# status_led_base.net
KiCad netlist of a schematic drawn in EAGLE
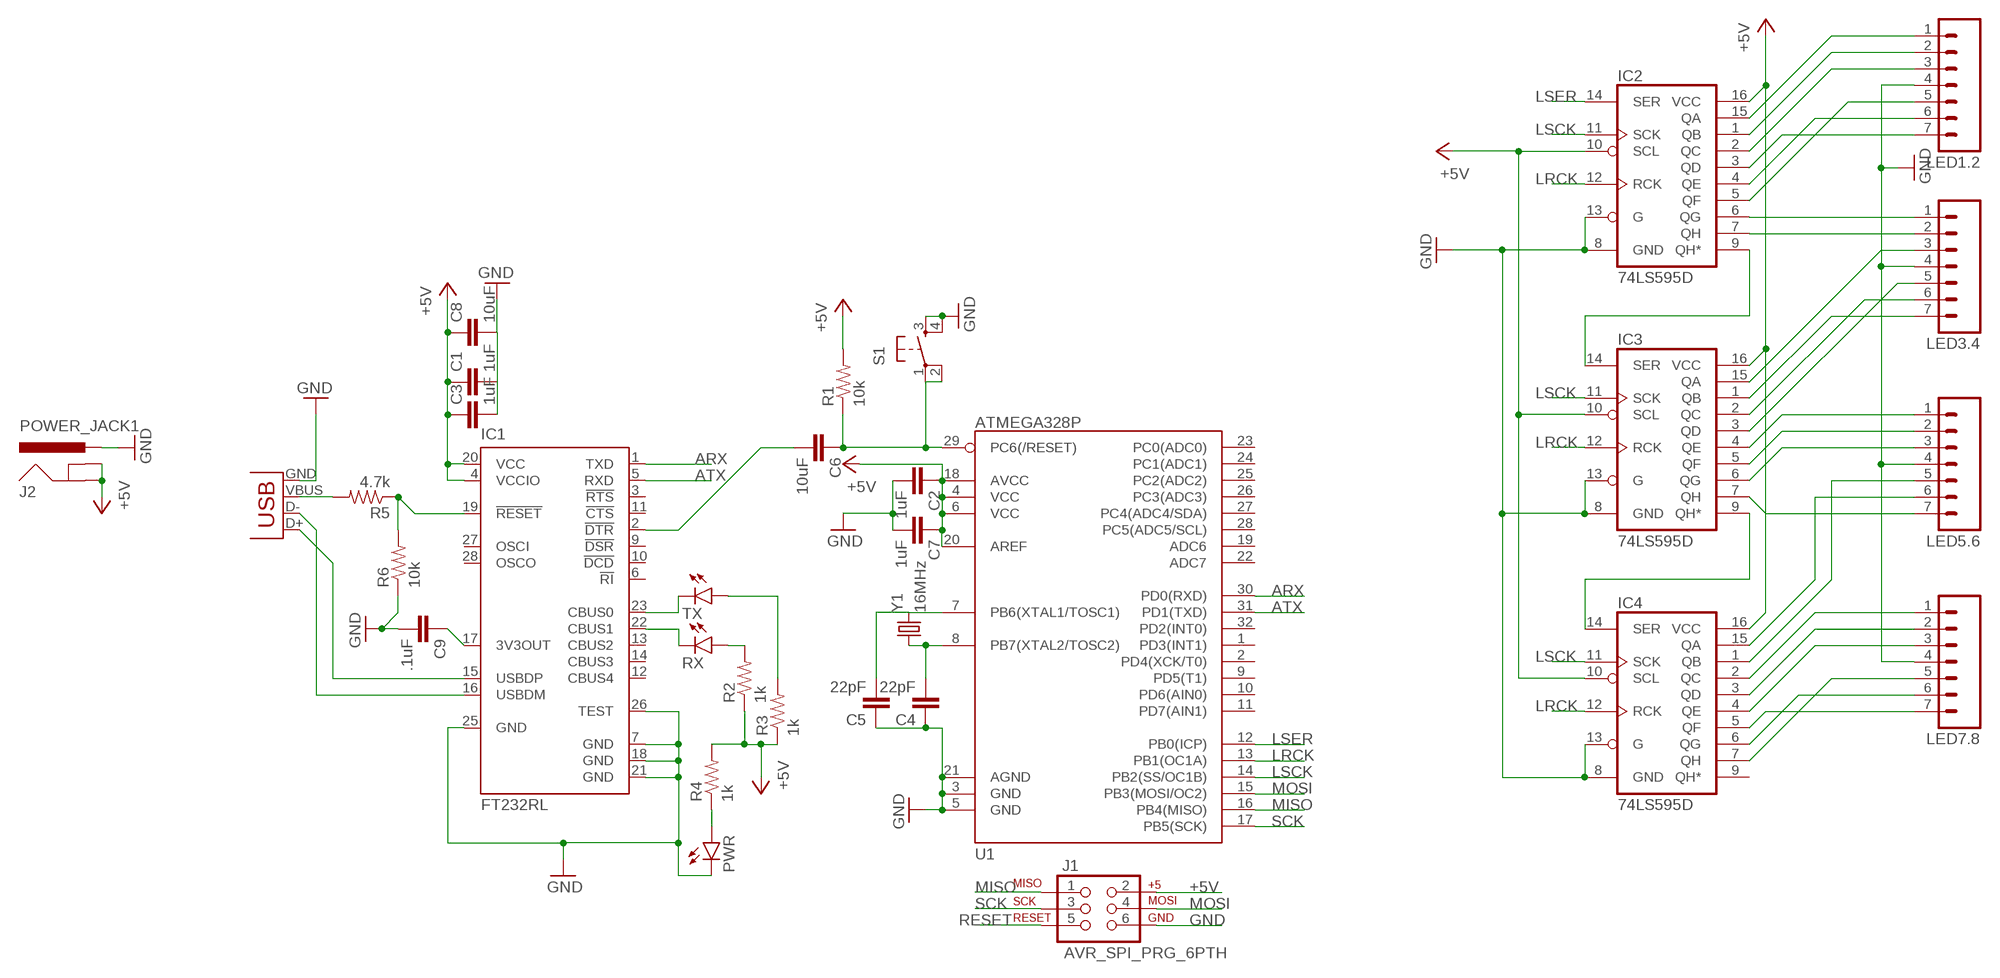
[diagram p0: schematic, sheet 1]

(export (version "E")
  (design (tool "Eeschema 10.0.6"))
  (components
    (comp (ref "C1")
      (value "1uF")
      (footprint "eagle-import:0603-CAP")
      (libsource (lib "eagle-import") (part "CAP0603-CAP"))
    )
    (comp (ref "C2")
      (value "1uF")
      (footprint "eagle-import:0603-CAP")
      (libsource (lib "eagle-import") (part "CAP0603-CAP"))
    )
    (comp (ref "C3")
      (value "1uF")
      (footprint "eagle-import:0603-CAP")
      (libsource (lib "eagle-import") (part "CAP0603-CAP"))
    )
    (comp (ref "C4")
      (value "22pF")
      (footprint "eagle-import:0603-CAP")
      (libsource (lib "eagle-import") (part "CAP0603-CAP"))
    )
    (comp (ref "C5")
      (value "22pF")
      (footprint "eagle-import:0603-CAP")
      (libsource (lib "eagle-import") (part "CAP0603-CAP"))
    )
    (comp (ref "C6")
      (value "10uF")
      (footprint "eagle-import:0603-CAP")
      (libsource (lib "eagle-import") (part "CAP0603-CAP"))
    )
    (comp (ref "C7")
      (value "1uF")
      (footprint "eagle-import:0603-CAP")
      (libsource (lib "eagle-import") (part "CAP0603-CAP"))
    )
    (comp (ref "C8")
      (value "10uF")
      (footprint "eagle-import:0603-CAP")
      (libsource (lib "eagle-import") (part "CAP0603-CAP"))
    )
    (comp (ref "C9")
      (value ".1uF")
      (footprint "eagle-import:0603-CAP")
      (libsource (lib "eagle-import") (part "CAP0603-CAP"))
    )
    (comp (ref "IC1")
      (value "FT232RL")
      (footprint "eagle-import:SSOP28")
      (libsource (lib "eagle-import") (part "FT232RL"))
    )
    (comp (ref "IC2")
      (value "74LS595D")
      (footprint "eagle-import:SO16")
      (libsource (lib "eagle-import") (part "74595DLS"))
    )
    (comp (ref "IC3")
      (value "74LS595D")
      (footprint "eagle-import:SO16")
      (libsource (lib "eagle-import") (part "74595DLS"))
    )
    (comp (ref "IC4")
      (value "74LS595D")
      (footprint "eagle-import:SO16")
      (libsource (lib "eagle-import") (part "74595DLS"))
    )
    (comp (ref "J1")
      (value "AVR_SPI_PRG_6PTH")
      (footprint "eagle-import:2X3")
      (libsource (lib "eagle-import") (part "AVR_SPI_PRG_6PTH"))
    )
    (comp (ref "J2")
      (value "POWER_JACK1")
      (footprint "eagle-import:POWER_JACK_SMD_OVERPASTE_REDBOARD_0603")
      (libsource (lib "eagle-import") (part "POWER_JACK1"))
    )
    (comp (ref "JP1")
      (value "USBSMD")
      (footprint "eagle-import:USB-MINIB")
      (libsource (lib "eagle-import") (part "USBSMD"))
    )
    (comp (ref "LED1.2")
      (value "M07")
      (footprint "eagle-import:1X07")
      (libsource (lib "eagle-import") (part "M07"))
    )
    (comp (ref "LED3.4")
      (value "M07")
      (footprint "eagle-import:1X07")
      (libsource (lib "eagle-import") (part "M07"))
    )
    (comp (ref "LED5.6")
      (value "M07")
      (footprint "eagle-import:1X07")
      (libsource (lib "eagle-import") (part "M07"))
    )
    (comp (ref "LED7.8")
      (value "M07")
      (footprint "eagle-import:1X07")
      (libsource (lib "eagle-import") (part "M07"))
    )
    (comp (ref "PWR")
      (value "LED0603")
      (footprint "eagle-import:LED-0603")
      (libsource (lib "eagle-import") (part "LED0603"))
    )
    (comp (ref "R1")
      (value "10k")
      (footprint "eagle-import:0603-RES")
      (libsource (lib "eagle-import") (part "RESISTOR0603-RES"))
    )
    (comp (ref "R2")
      (value "1k")
      (footprint "eagle-import:0603-RES")
      (libsource (lib "eagle-import") (part "RESISTOR0603-RES"))
    )
    (comp (ref "R3")
      (value "1k")
      (footprint "eagle-import:0603-RES")
      (libsource (lib "eagle-import") (part "RESISTOR0603-RES"))
    )
    (comp (ref "R4")
      (value "1k")
      (footprint "eagle-import:0603-RES")
      (libsource (lib "eagle-import") (part "RESISTOR0603-RES"))
    )
    (comp (ref "R5")
      (value "4.7k")
      (footprint "eagle-import:0603-RES")
      (libsource (lib "eagle-import") (part "RESISTOR0603-RES"))
    )
    (comp (ref "R6")
      (value "10k")
      (footprint "eagle-import:0603-RES")
      (libsource (lib "eagle-import") (part "RESISTOR0603-RES"))
    )
    (comp (ref "RX")
      (value "LED0603")
      (footprint "eagle-import:LED-0603")
      (libsource (lib "eagle-import") (part "LED0603"))
    )
    (comp (ref "S1")
      (value "TAC_SWITCHSMD")
      (footprint "eagle-import:TACTILE-SWITCH-SMD")
      (libsource (lib "eagle-import") (part "TAC_SWITCHSMD"))
    )
    (comp (ref "TX")
      (value "LED0603")
      (footprint "eagle-import:LED-0603")
      (libsource (lib "eagle-import") (part "LED0603"))
    )
    (comp (ref "U1")
      (value "ATMEGA328P")
      (footprint "eagle-import:TQFP32-08")
      (libsource (lib "eagle-import") (part "ATMEGA328_SMT"))
    )
    (comp (ref "Y1")
      (value "16MHz")
      (footprint "eagle-import:HC49UP")
      (libsource (lib "eagle-import") (part "CRYSTALSMD"))
    )
  )
  (nets
    (net (code "1") (name "+5V") (class "Default")
      (node (ref "C1") (pin "1") (pinfunction "1_1") (pintype "passive"))
      (node (ref "C2") (pin "1") (pinfunction "1_1") (pintype "passive"))
      (node (ref "C3") (pin "1") (pinfunction "1_1") (pintype "passive"))
      (node (ref "C7") (pin "1") (pinfunction "1_1") (pintype "passive"))
      (node (ref "C8") (pin "1") (pinfunction "1_1") (pintype "passive"))
      (node (ref "IC1") (pin "20") (pinfunction "VCC_20") (pintype "power_in"))
      (node (ref "IC1") (pin "4") (pinfunction "VCCIO_4") (pintype "power_in"))
      (node (ref "IC2") (pin "10") (pinfunction "SCL_10") (pintype "input"))
      (node (ref "IC2") (pin "16") (pinfunction "VCC_16") (pintype "power_in"))
      (node (ref "IC3") (pin "10") (pinfunction "SCL_10") (pintype "input"))
      (node (ref "IC3") (pin "16") (pinfunction "VCC_16") (pintype "power_in"))
      (node (ref "IC4") (pin "10") (pinfunction "SCL_10") (pintype "input"))
      (node (ref "IC4") (pin "16") (pinfunction "VCC_16") (pintype "power_in"))
      (node (ref "J1") (pin "2") (pinfunction "2_2") (pintype "passive"))
      (node (ref "J2") (pin "GND") (pinfunction "GNDBREAK_GND") (pintype "bidirectional"))
      (node (ref "J2") (pin "P$4") (pinfunction "GND_P$4") (pintype "bidirectional"))
      (node (ref "R1") (pin "2") (pinfunction "2_2") (pintype "passive"))
      (node (ref "R2") (pin "1") (pinfunction "1_1") (pintype "passive"))
      (node (ref "R3") (pin "1") (pinfunction "1_1") (pintype "passive"))
      (node (ref "R4") (pin "2") (pinfunction "2_2") (pintype "passive"))
      (node (ref "U1") (pin "18") (pinfunction "AVCC_18") (pintype "bidirectional"))
      (node (ref "U1") (pin "20") (pinfunction "AREF_20") (pintype "bidirectional"))
      (node (ref "U1") (pin "4") (pinfunction "VCC_4") (pintype "bidirectional"))
      (node (ref "U1") (pin "6") (pinfunction "VCC_6") (pintype "bidirectional"))
    )
    (net (code "2") (name "/ARX") (class "Default")
      (node (ref "IC1") (pin "1") (pinfunction "TXD_1") (pintype "output"))
      (node (ref "U1") (pin "30") (pinfunction "PD0(RXD)_30") (pintype "bidirectional"))
    )
    (net (code "3") (name "/ATX") (class "Default")
      (node (ref "IC1") (pin "5") (pinfunction "RXD_5") (pintype "input"))
      (node (ref "U1") (pin "31") (pinfunction "PD1(TXD)_31") (pintype "bidirectional"))
    )
    (net (code "4") (name "/LRCK") (class "Default")
      (node (ref "IC2") (pin "12") (pinfunction "RCK_12") (pintype "input"))
      (node (ref "IC3") (pin "12") (pinfunction "RCK_12") (pintype "input"))
      (node (ref "IC4") (pin "12") (pinfunction "RCK_12") (pintype "input"))
      (node (ref "U1") (pin "13") (pinfunction "PB1(OC1A)_13") (pintype "bidirectional"))
    )
    (net (code "5") (name "/LSCK") (class "Default")
      (node (ref "IC2") (pin "11") (pinfunction "SCK_11") (pintype "input"))
      (node (ref "IC3") (pin "11") (pinfunction "SCK_11") (pintype "input"))
      (node (ref "IC4") (pin "11") (pinfunction "SCK_11") (pintype "input"))
      (node (ref "U1") (pin "14") (pinfunction "PB2(SS/OC1B)_14") (pintype "bidirectional"))
    )
    (net (code "6") (name "/LSER") (class "Default")
      (node (ref "IC2") (pin "14") (pinfunction "SER_14") (pintype "input"))
      (node (ref "U1") (pin "12") (pinfunction "PB0(ICP)_12") (pintype "bidirectional"))
    )
    (net (code "7") (name "/MISO") (class "Default")
      (node (ref "J1") (pin "1") (pinfunction "1_1") (pintype "passive"))
      (node (ref "U1") (pin "16") (pinfunction "PB4(MISO)_16") (pintype "bidirectional"))
    )
    (net (code "8") (name "/MOSI") (class "Default")
      (node (ref "J1") (pin "4") (pinfunction "4_4") (pintype "passive"))
      (node (ref "U1") (pin "15") (pinfunction "PB3(MOSI/OC2)_15") (pintype "bidirectional"))
    )
    (net (code "9") (name "/RESET") (class "Default")
      (node (ref "C6") (pin "1") (pinfunction "1_1") (pintype "passive"))
      (node (ref "J1") (pin "5") (pinfunction "5_5") (pintype "passive"))
      (node (ref "R1") (pin "1") (pinfunction "1_1") (pintype "passive"))
      (node (ref "S1") (pin "1") (pinfunction "1_1") (pintype "passive"))
      (node (ref "S1") (pin "2") (pinfunction "2_2") (pintype "passive"))
      (node (ref "U1") (pin "29") (pinfunction "PC6(/RESET)_29") (pintype "bidirectional"))
    )
    (net (code "10") (name "/SCK") (class "Default")
      (node (ref "J1") (pin "3") (pinfunction "3_3") (pintype "passive"))
      (node (ref "U1") (pin "17") (pinfunction "PB5(SCK)_17") (pintype "bidirectional"))
    )
    (net (code "11") (name "GND") (class "Default")
      (node (ref "C1") (pin "2") (pinfunction "2_2") (pintype "passive"))
      (node (ref "C2") (pin "2") (pinfunction "2_2") (pintype "passive"))
      (node (ref "C3") (pin "2") (pinfunction "2_2") (pintype "passive"))
      (node (ref "C4") (pin "1") (pinfunction "1_1") (pintype "passive"))
      (node (ref "C5") (pin "1") (pinfunction "1_1") (pintype "passive"))
      (node (ref "C7") (pin "2") (pinfunction "2_2") (pintype "passive"))
      (node (ref "C8") (pin "2") (pinfunction "2_2") (pintype "passive"))
      (node (ref "C9") (pin "2") (pinfunction "2_2") (pintype "passive"))
      (node (ref "IC1") (pin "18") (pinfunction "GND_18") (pintype "power_in"))
      (node (ref "IC1") (pin "21") (pinfunction "GND_21") (pintype "power_in"))
      (node (ref "IC1") (pin "25") (pinfunction "GND_25") (pintype "power_in"))
      (node (ref "IC1") (pin "26") (pinfunction "TEST_26") (pintype "input"))
      (node (ref "IC1") (pin "7") (pinfunction "GND_7") (pintype "power_in"))
      (node (ref "IC2") (pin "13") (pinfunction "G_13") (pintype "input"))
      (node (ref "IC2") (pin "8") (pinfunction "GND_8") (pintype "power_in"))
      (node (ref "IC3") (pin "13") (pinfunction "G_13") (pintype "input"))
      (node (ref "IC3") (pin "8") (pinfunction "GND_8") (pintype "power_in"))
      (node (ref "IC4") (pin "13") (pinfunction "G_13") (pintype "input"))
      (node (ref "IC4") (pin "8") (pinfunction "GND_8") (pintype "power_in"))
      (node (ref "J1") (pin "6") (pinfunction "6_6") (pintype "passive"))
      (node (ref "J2") (pin "VIN0") (pinfunction "PWR_VIN0") (pintype "bidirectional"))
      (node (ref "JP1") (pin "GND") (pinfunction "GND_GND") (pintype "bidirectional"))
      (node (ref "LED1.2") (pin "4") (pinfunction "4_4") (pintype "passive"))
      (node (ref "LED3.4") (pin "4") (pinfunction "4_4") (pintype "passive"))
      (node (ref "LED5.6") (pin "4") (pinfunction "4_4") (pintype "passive"))
      (node (ref "LED7.8") (pin "4") (pinfunction "4_4") (pintype "passive"))
      (node (ref "PWR") (pin "C") (pinfunction "C_C") (pintype "passive"))
      (node (ref "R6") (pin "1") (pinfunction "1_1") (pintype "passive"))
      (node (ref "S1") (pin "3") (pinfunction "3_3") (pintype "passive"))
      (node (ref "S1") (pin "4") (pinfunction "4_4") (pintype "passive"))
      (node (ref "U1") (pin "21") (pinfunction "AGND_21") (pintype "bidirectional"))
      (node (ref "U1") (pin "3") (pinfunction "GND_3") (pintype "bidirectional"))
      (node (ref "U1") (pin "5") (pinfunction "GND_5") (pintype "bidirectional"))
    )
    (net (code "12") (name "Net-(IC1-3V3OUT)") (class "Default")
      (node (ref "C9") (pin "1") (pinfunction "1_1") (pintype "passive"))
      (node (ref "IC1") (pin "17") (pinfunction "3V3OUT_17") (pintype "output"))
    )
    (net (code "13") (name "Net-(IC1-CBUS0)") (class "Default")
      (node (ref "IC1") (pin "23") (pinfunction "CBUS0_23") (pintype "bidirectional"))
      (node (ref "TX") (pin "C") (pinfunction "C_C") (pintype "passive"))
    )
    (net (code "14") (name "Net-(IC1-CBUS1)") (class "Default")
      (node (ref "IC1") (pin "22") (pinfunction "CBUS1_22") (pintype "bidirectional"))
      (node (ref "RX") (pin "C") (pinfunction "C_C") (pintype "passive"))
    )
    (net (code "15") (name "Net-(IC1-USBDM)") (class "Default")
      (node (ref "IC1") (pin "16") (pinfunction "USBDM_16") (pintype "bidirectional"))
      (node (ref "JP1") (pin "D-") (pinfunction "D-_D-") (pintype "bidirectional"))
    )
    (net (code "16") (name "Net-(IC1-USBDP)") (class "Default")
      (node (ref "IC1") (pin "15") (pinfunction "USBDP_15") (pintype "bidirectional"))
      (node (ref "JP1") (pin "D+") (pinfunction "D+_D+") (pintype "bidirectional"))
    )
    (net (code "17") (name "Net-(IC1-~{DTR})") (class "Default")
      (node (ref "C6") (pin "2") (pinfunction "2_2") (pintype "passive"))
      (node (ref "IC1") (pin "2") (pinfunction "~{DTR}_2") (pintype "output"))
    )
    (net (code "18") (name "Net-(IC1-~{RESET})") (class "Default")
      (node (ref "IC1") (pin "19") (pinfunction "~{RESET}_19") (pintype "input"))
      (node (ref "R5") (pin "1") (pinfunction "1_1") (pintype "passive"))
      (node (ref "R6") (pin "2") (pinfunction "2_2") (pintype "passive"))
    )
    (net (code "19") (name "Net-(IC2-QA)") (class "Default")
      (node (ref "IC2") (pin "15") (pinfunction "QA_15") (pintype "tri_state"))
      (node (ref "LED1.2") (pin "1") (pinfunction "1_1") (pintype "passive"))
    )
    (net (code "20") (name "Net-(IC2-QB)") (class "Default")
      (node (ref "IC2") (pin "1") (pinfunction "QB_1") (pintype "tri_state"))
      (node (ref "LED1.2") (pin "2") (pinfunction "2_2") (pintype "passive"))
    )
    (net (code "21") (name "Net-(IC2-QC)") (class "Default")
      (node (ref "IC2") (pin "2") (pinfunction "QC_2") (pintype "tri_state"))
      (node (ref "LED1.2") (pin "3") (pinfunction "3_3") (pintype "passive"))
    )
    (net (code "22") (name "Net-(IC2-QD)") (class "Default")
      (node (ref "IC2") (pin "3") (pinfunction "QD_3") (pintype "tri_state"))
      (node (ref "LED1.2") (pin "7") (pinfunction "7_7") (pintype "passive"))
    )
    (net (code "23") (name "Net-(IC2-QE)") (class "Default")
      (node (ref "IC2") (pin "4") (pinfunction "QE_4") (pintype "tri_state"))
      (node (ref "LED1.2") (pin "6") (pinfunction "6_6") (pintype "passive"))
    )
    (net (code "24") (name "Net-(IC2-QF)") (class "Default")
      (node (ref "IC2") (pin "5") (pinfunction "QF_5") (pintype "tri_state"))
      (node (ref "LED1.2") (pin "5") (pinfunction "5_5") (pintype "passive"))
    )
    (net (code "25") (name "Net-(IC2-QG)") (class "Default")
      (node (ref "IC2") (pin "6") (pinfunction "QG_6") (pintype "tri_state"))
      (node (ref "LED3.4") (pin "1") (pinfunction "1_1") (pintype "passive"))
    )
    (net (code "26") (name "Net-(IC2-QH)") (class "Default")
      (node (ref "IC2") (pin "7") (pinfunction "QH_7") (pintype "tri_state"))
      (node (ref "LED3.4") (pin "2") (pinfunction "2_2") (pintype "passive"))
    )
    (net (code "27") (name "Net-(IC2-QH*)") (class "Default")
      (node (ref "IC2") (pin "9") (pinfunction "QH*_9") (pintype "tri_state"))
      (node (ref "IC3") (pin "14") (pinfunction "SER_14") (pintype "input"))
    )
    (net (code "28") (name "Net-(IC3-QA)") (class "Default")
      (node (ref "IC3") (pin "15") (pinfunction "QA_15") (pintype "tri_state"))
      (node (ref "LED3.4") (pin "3") (pinfunction "3_3") (pintype "passive"))
    )
    (net (code "29") (name "Net-(IC3-QB)") (class "Default")
      (node (ref "IC3") (pin "1") (pinfunction "QB_1") (pintype "tri_state"))
      (node (ref "LED3.4") (pin "7") (pinfunction "7_7") (pintype "passive"))
    )
    (net (code "30") (name "Net-(IC3-QC)") (class "Default")
      (node (ref "IC3") (pin "2") (pinfunction "QC_2") (pintype "tri_state"))
      (node (ref "LED3.4") (pin "6") (pinfunction "6_6") (pintype "passive"))
    )
    (net (code "31") (name "Net-(IC3-QD)") (class "Default")
      (node (ref "IC3") (pin "3") (pinfunction "QD_3") (pintype "tri_state"))
      (node (ref "LED3.4") (pin "5") (pinfunction "5_5") (pintype "passive"))
    )
    (net (code "32") (name "Net-(IC3-QE)") (class "Default")
      (node (ref "IC3") (pin "4") (pinfunction "QE_4") (pintype "tri_state"))
      (node (ref "LED5.6") (pin "1") (pinfunction "1_1") (pintype "passive"))
    )
    (net (code "33") (name "Net-(IC3-QF)") (class "Default")
      (node (ref "IC3") (pin "5") (pinfunction "QF_5") (pintype "tri_state"))
      (node (ref "LED5.6") (pin "2") (pinfunction "2_2") (pintype "passive"))
    )
    (net (code "34") (name "Net-(IC3-QG)") (class "Default")
      (node (ref "IC3") (pin "6") (pinfunction "QG_6") (pintype "tri_state"))
      (node (ref "LED5.6") (pin "3") (pinfunction "3_3") (pintype "passive"))
    )
    (net (code "35") (name "Net-(IC3-QH)") (class "Default")
      (node (ref "IC3") (pin "7") (pinfunction "QH_7") (pintype "tri_state"))
      (node (ref "LED5.6") (pin "7") (pinfunction "7_7") (pintype "passive"))
    )
    (net (code "36") (name "Net-(IC3-QH*)") (class "Default")
      (node (ref "IC3") (pin "9") (pinfunction "QH*_9") (pintype "tri_state"))
      (node (ref "IC4") (pin "14") (pinfunction "SER_14") (pintype "input"))
    )
    (net (code "37") (name "Net-(IC4-QA)") (class "Default")
      (node (ref "IC4") (pin "15") (pinfunction "QA_15") (pintype "tri_state"))
      (node (ref "LED5.6") (pin "6") (pinfunction "6_6") (pintype "passive"))
    )
    (net (code "38") (name "Net-(IC4-QB)") (class "Default")
      (node (ref "IC4") (pin "1") (pinfunction "QB_1") (pintype "tri_state"))
      (node (ref "LED5.6") (pin "5") (pinfunction "5_5") (pintype "passive"))
    )
    (net (code "39") (name "Net-(IC4-QC)") (class "Default")
      (node (ref "IC4") (pin "2") (pinfunction "QC_2") (pintype "tri_state"))
      (node (ref "LED7.8") (pin "1") (pinfunction "1_1") (pintype "passive"))
    )
    (net (code "40") (name "Net-(IC4-QD)") (class "Default")
      (node (ref "IC4") (pin "3") (pinfunction "QD_3") (pintype "tri_state"))
      (node (ref "LED7.8") (pin "2") (pinfunction "2_2") (pintype "passive"))
    )
    (net (code "41") (name "Net-(IC4-QE)") (class "Default")
      (node (ref "IC4") (pin "4") (pinfunction "QE_4") (pintype "tri_state"))
      (node (ref "LED7.8") (pin "3") (pinfunction "3_3") (pintype "passive"))
    )
    (net (code "42") (name "Net-(IC4-QF)") (class "Default")
      (node (ref "IC4") (pin "5") (pinfunction "QF_5") (pintype "tri_state"))
      (node (ref "LED7.8") (pin "7") (pinfunction "7_7") (pintype "passive"))
    )
    (net (code "43") (name "Net-(IC4-QG)") (class "Default")
      (node (ref "IC4") (pin "6") (pinfunction "QG_6") (pintype "tri_state"))
      (node (ref "LED7.8") (pin "6") (pinfunction "6_6") (pintype "passive"))
    )
    (net (code "44") (name "Net-(IC4-QH)") (class "Default")
      (node (ref "IC4") (pin "7") (pinfunction "QH_7") (pintype "tri_state"))
      (node (ref "LED7.8") (pin "5") (pinfunction "5_5") (pintype "passive"))
    )
    (net (code "45") (name "Net-(JP1-PadVBUS)") (class "Default")
      (node (ref "JP1") (pin "VBUS") (pinfunction "VBUS_VBUS") (pintype "bidirectional"))
      (node (ref "R5") (pin "2") (pinfunction "2_2") (pintype "passive"))
    )
    (net (code "46") (name "Net-(PWR-PadA)") (class "Default")
      (node (ref "PWR") (pin "A") (pinfunction "A_A") (pintype "passive"))
      (node (ref "R4") (pin "1") (pinfunction "1_1") (pintype "passive"))
    )
    (net (code "47") (name "Net-(R2-Pad2)") (class "Default")
      (node (ref "R2") (pin "2") (pinfunction "2_2") (pintype "passive"))
      (node (ref "RX") (pin "A") (pinfunction "A_A") (pintype "passive"))
    )
    (net (code "48") (name "Net-(R3-Pad2)") (class "Default")
      (node (ref "R3") (pin "2") (pinfunction "2_2") (pintype "passive"))
      (node (ref "TX") (pin "A") (pinfunction "A_A") (pintype "passive"))
    )
    (net (code "49") (name "Net-(U1-PB6(XTAL1{slash}TOSC1))") (class "Default")
      (node (ref "C5") (pin "2") (pinfunction "2_2") (pintype "passive"))
      (node (ref "U1") (pin "7") (pinfunction "PB6(XTAL1/TOSC1)_7") (pintype "bidirectional"))
      (node (ref "Y1") (pin "2") (pinfunction "2_2") (pintype "passive"))
    )
    (net (code "50") (name "Net-(U1-PB7(XTAL2{slash}TOSC2))") (class "Default")
      (node (ref "C4") (pin "2") (pinfunction "2_2") (pintype "passive"))
      (node (ref "U1") (pin "8") (pinfunction "PB7(XTAL2/TOSC2)_8") (pintype "bidirectional"))
      (node (ref "Y1") (pin "1") (pinfunction "1_1") (pintype "passive"))
    )
    (net (code "51") (name "unconnected-(IC1-CBUS2-Pad13)") (class "Default")
      (node (ref "IC1") (pin "13") (pinfunction "CBUS2_13") (pintype "bidirectional"))
    )
    (net (code "52") (name "unconnected-(IC1-CBUS3-Pad14)") (class "Default")
      (node (ref "IC1") (pin "14") (pinfunction "CBUS3_14") (pintype "bidirectional"))
    )
    (net (code "53") (name "unconnected-(IC1-CBUS4-Pad12)") (class "Default")
      (node (ref "IC1") (pin "12") (pinfunction "CBUS4_12") (pintype "bidirectional"))
    )
    (net (code "54") (name "unconnected-(IC1-OSCI-Pad27)") (class "Default")
      (node (ref "IC1") (pin "27") (pinfunction "OSCI_27") (pintype "input"))
    )
    (net (code "55") (name "unconnected-(IC1-OSCO-Pad28)") (class "Default")
      (node (ref "IC1") (pin "28") (pinfunction "OSCO_28") (pintype "output"))
    )
    (net (code "56") (name "unconnected-(IC1-~{CTS}-Pad11)") (class "Default")
      (node (ref "IC1") (pin "11") (pinfunction "~{CTS}_11") (pintype "input"))
    )
    (net (code "57") (name "unconnected-(IC1-~{DCD}-Pad10)") (class "Default")
      (node (ref "IC1") (pin "10") (pinfunction "~{DCD}_10") (pintype "input"))
    )
    (net (code "58") (name "unconnected-(IC1-~{DSR}-Pad9)") (class "Default")
      (node (ref "IC1") (pin "9") (pinfunction "~{DSR}_9") (pintype "input"))
    )
    (net (code "59") (name "unconnected-(IC1-~{RI}-Pad6)") (class "Default")
      (node (ref "IC1") (pin "6") (pinfunction "~{RI}_6") (pintype "input"))
    )
    (net (code "60") (name "unconnected-(IC1-~{RTS}-Pad3)") (class "Default")
      (node (ref "IC1") (pin "3") (pinfunction "~{RTS}_3") (pintype "output"))
    )
    (net (code "61") (name "unconnected-(IC4-QH*-Pad9)") (class "Default")
      (node (ref "IC4") (pin "9") (pinfunction "QH*_9") (pintype "tri_state"))
    )
    (net (code "62") (name "unconnected-(U1-ADC6-Pad19)") (class "Default")
      (node (ref "U1") (pin "19") (pinfunction "ADC6_19") (pintype "bidirectional"))
    )
    (net (code "63") (name "unconnected-(U1-ADC7-Pad22)") (class "Default")
      (node (ref "U1") (pin "22") (pinfunction "ADC7_22") (pintype "bidirectional"))
    )
    (net (code "64") (name "unconnected-(U1-PC0(ADC0)-Pad23)") (class "Default")
      (node (ref "U1") (pin "23") (pinfunction "PC0(ADC0)_23") (pintype "bidirectional"))
    )
    (net (code "65") (name "unconnected-(U1-PC1(ADC1)-Pad24)") (class "Default")
      (node (ref "U1") (pin "24") (pinfunction "PC1(ADC1)_24") (pintype "bidirectional"))
    )
    (net (code "66") (name "unconnected-(U1-PC2(ADC2)-Pad25)") (class "Default")
      (node (ref "U1") (pin "25") (pinfunction "PC2(ADC2)_25") (pintype "bidirectional"))
    )
    (net (code "67") (name "unconnected-(U1-PC3(ADC3)-Pad26)") (class "Default")
      (node (ref "U1") (pin "26") (pinfunction "PC3(ADC3)_26") (pintype "bidirectional"))
    )
    (net (code "68") (name "unconnected-(U1-PC4(ADC4{slash}SDA)-Pad27)") (class "Default")
      (node (ref "U1") (pin "27") (pinfunction "PC4(ADC4/SDA)_27") (pintype "bidirectional"))
    )
    (net (code "69") (name "unconnected-(U1-PC5(ADC5{slash}SCL)-Pad28)") (class "Default")
      (node (ref "U1") (pin "28") (pinfunction "PC5(ADC5/SCL)_28") (pintype "bidirectional"))
    )
    (net (code "70") (name "unconnected-(U1-PD2(INT0)-Pad32)") (class "Default")
      (node (ref "U1") (pin "32") (pinfunction "PD2(INT0)_32") (pintype "bidirectional"))
    )
    (net (code "71") (name "unconnected-(U1-PD3(INT1)-Pad1)") (class "Default")
      (node (ref "U1") (pin "1") (pinfunction "PD3(INT1)_1") (pintype "bidirectional"))
    )
    (net (code "72") (name "unconnected-(U1-PD4(XCK{slash}T0)-Pad2)") (class "Default")
      (node (ref "U1") (pin "2") (pinfunction "PD4(XCK/T0)_2") (pintype "bidirectional"))
    )
    (net (code "73") (name "unconnected-(U1-PD5(T1)-Pad9)") (class "Default")
      (node (ref "U1") (pin "9") (pinfunction "PD5(T1)_9") (pintype "bidirectional"))
    )
    (net (code "74") (name "unconnected-(U1-PD6(AIN0)-Pad10)") (class "Default")
      (node (ref "U1") (pin "10") (pinfunction "PD6(AIN0)_10") (pintype "bidirectional"))
    )
    (net (code "75") (name "unconnected-(U1-PD7(AIN1)-Pad11)") (class "Default")
      (node (ref "U1") (pin "11") (pinfunction "PD7(AIN1)_11") (pintype "bidirectional"))
    )
  )
)
